# GNSS_MB.net
KiCad netlist of a schematic drawn in Altium Designer
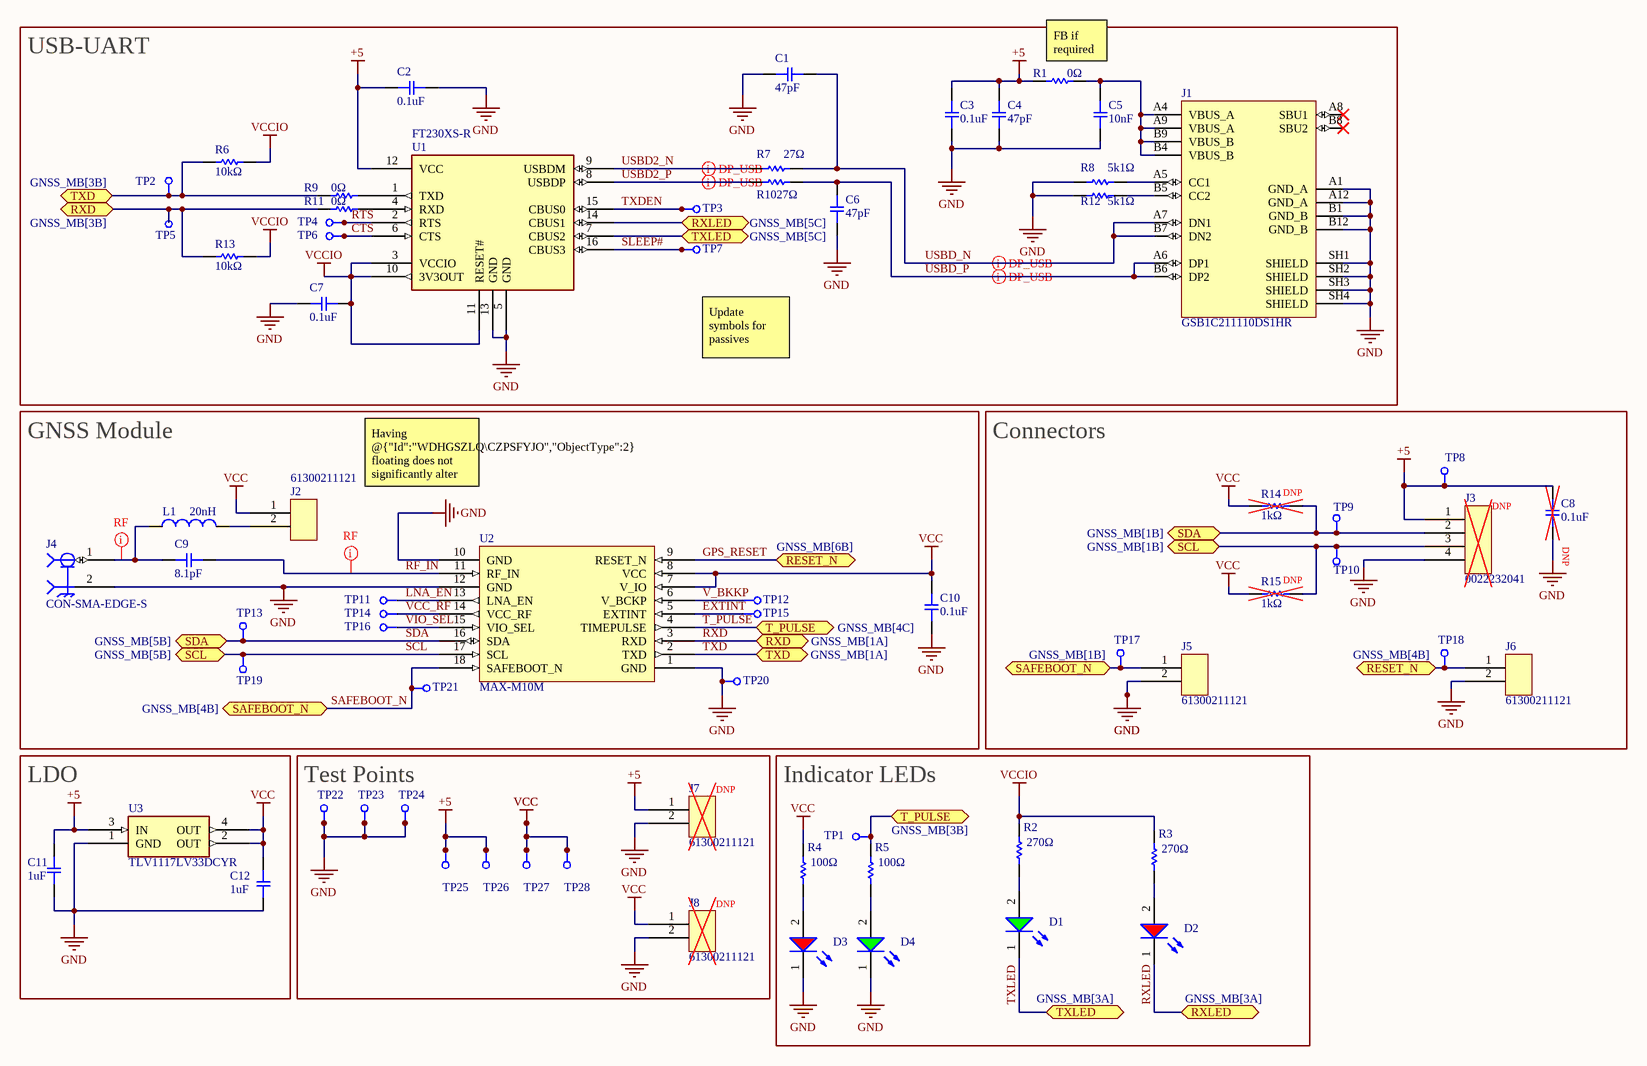
[diagram p0: GNSS_MB.SchDoc]

(export (version "E")
  (design (tool "Eeschema 10.0.6"))
  (components
    (comp (ref "C1")
      (value "GCM188L81H104KA57D")
      (footprint "CAP_MURATA_0603")
      (description "CAP CER 0.1UF 50V X8L 0603")
      (fields (field (name "CAPACITANCE") "47pF"))
      (libsource (lib "Symbols") (part "GCM188L81H104KA57D"))
    )
    (comp (ref "C2")
      (value "GCM188L81H104KA57D")
      (footprint "CAP_MURATA_0603")
      (description "CAP CER 0.1UF 50V X8L 0603")
      (fields (field (name "CAPACITANCE") "0.1uF"))
      (libsource (lib "Symbols") (part "GCM188L81H104KA57D"))
    )
    (comp (ref "C3")
      (value "GCM188L81H104KA57D")
      (footprint "CAP_MURATA_0603")
      (description "CAP CER 0.1UF 50V X8L 0603")
      (fields (field (name "CAPACITANCE") "0.1uF"))
      (libsource (lib "Symbols") (part "GCM188L81H104KA57D"))
    )
    (comp (ref "C4")
      (value "GCM188L81H104KA57D")
      (footprint "CAP_MURATA_0603")
      (description "CAP CER 0.1UF 50V X8L 0603")
      (fields (field (name "CAPACITANCE") "47pF"))
      (libsource (lib "Symbols") (part "GCM188L81H104KA57D"))
    )
    (comp (ref "C5")
      (value "GCM188L81H104KA57D")
      (footprint "CAP_MURATA_0603")
      (description "CAP CER 0.1UF 50V X8L 0603")
      (fields (field (name "CAPACITANCE") "10nF"))
      (libsource (lib "Symbols") (part "GCM188L81H104KA57D"))
    )
    (comp (ref "C6")
      (value "GCM188L81H104KA57D")
      (footprint "CAP_MURATA_0603")
      (description "CAP CER 0.1UF 50V X8L 0603")
      (fields (field (name "CAPACITANCE") "47pF"))
      (libsource (lib "Symbols") (part "GCM188L81H104KA57D"))
    )
    (comp (ref "C7")
      (value "GCM188L81H104KA57D")
      (footprint "CAP_MURATA_0603")
      (description "CAP CER 0.1UF 50V X8L 0603")
      (fields (field (name "CAPACITANCE") "0.1uF"))
      (libsource (lib "Symbols") (part "GCM188L81H104KA57D"))
    )
    (comp (ref "C8")
      (value "GCM188L81H104KA57D")
      (footprint "CAP_MURATA_0603")
      (description "CAP CER 0.1UF 50V X8L 0603")
      (fields (field (name "CAPACITANCE") "0.1uF"))
      (libsource (lib "Symbols") (part "GCM188L81H104KA57D"))
    )
    (comp (ref "C9")
      (value "GCM188L81H104KA57D")
      (footprint "CAP_MURATA_0603")
      (description "CAP CER 0.1UF 50V X8L 0603")
      (fields (field (name "CAPACITANCE") "8.1pF"))
      (libsource (lib "Symbols") (part "GCM188L81H104KA57D"))
    )
    (comp (ref "C10")
      (value "GCM188L81H104KA57D")
      (footprint "CAP_MURATA_0603")
      (description "CAP CER 0.1UF 50V X8L 0603")
      (fields (field (name "CAPACITANCE") "0.1uF"))
      (libsource (lib "Symbols") (part "GCM188L81H104KA57D"))
    )
    (comp (ref "C11")
      (value "GRM188R61A105KA61D")
      (footprint "CAP_MURATA_0603")
      (description "CAP CER 1UF 10V X5R 0603")
      (fields (field (name "CAPACITANCE") "1uF"))
      (libsource (lib "Symbols") (part "GRM188R61A105KA61D"))
    )
    (comp (ref "C12")
      (value "GRM188R61A105KA61D")
      (footprint "CAP_MURATA_0603")
      (description "CAP CER 1UF 10V X5R 0603")
      (fields (field (name "CAPACITANCE") "1uF"))
      (libsource (lib "Symbols") (part "GRM188R61A105KA61D"))
    )
    (comp (ref "D1")
      (value "Green, 3.2V, 140°")
      (footprint "WL-SMCW - duplicate")
      (description "WL-SMCW Mono-color Chip LED Waterclear, SMT, size 0603, Green, 3.2V, 140°")
      (fields
        (field (name "MANUFACTURER PART NUMBER") "150060GS75000")
        (field (name "MANUFACTURER") "Wurth Elektronik")
      )
      (libsource (lib "Symbols") (part "150060GS75000"))
    )
    (comp (ref "D2")
      (value "Red, 2V, 140°")
      (footprint "WL-SMCW - duplicate")
      (description "WL-SMCW Mono-color Chip LED Waterclear, SMT, size 0603, Red, 2V, 140°")
      (fields
        (field (name "MANUFACTURER PART NUMBER") "150060RS75000")
        (field (name "MANUFACTURER") "Wurth Elektronik")
      )
      (libsource (lib "Symbols") (part "150060RS75000"))
    )
    (comp (ref "D3")
      (value "Red, 2V, 140°")
      (footprint "WL-SMCW - duplicate")
      (description "WL-SMCW Mono-color Chip LED Waterclear, SMT, size 0603, Red, 2V, 140°")
      (fields
        (field (name "MANUFACTURER PART NUMBER") "150060RS75000")
        (field (name "MANUFACTURER") "Wurth Elektronik")
      )
      (libsource (lib "Symbols") (part "150060RS75000"))
    )
    (comp (ref "D4")
      (value "Green, 3.2V, 140°")
      (footprint "WL-SMCW - duplicate")
      (description "WL-SMCW Mono-color Chip LED Waterclear, SMT, size 0603, Green, 3.2V, 140°")
      (fields
        (field (name "MANUFACTURER PART NUMBER") "150060GS75000")
        (field (name "MANUFACTURER") "Wurth Elektronik")
      )
      (libsource (lib "Symbols") (part "150060GS75000"))
    )
    (comp (ref "J1")
      (value "GSB1C211110DS1HR")
      (footprint "AMPHENOL_GSB1C211110DS1HR")
      (description "USB2.0, Type C, Top mount, Center Height 1.78mm, Dual Row DIP")
      (fields (field (name "MF") "Amphenol Canada"))
      (libsource (lib "Symbols") (part "GSB1C211110DS1HR"))
    )
    (comp (ref "J2")
      (value "61300211121")
      (footprint "61300211121")
      (description "CONN HEADER VERT 2POS 2.54MM")
      (libsource (lib "Symbols") (part "61300211121"))
    )
    (comp (ref "J3")
      (value "0022232041")
      (footprint "CONN HEADER VERT 4POS 2.54MM")
      (description "CONN HEADER VERT 4POS 2.54MM")
      (libsource (lib "Symbols") (part "0022232041"))
    )
    (comp (ref "J4")
      (value "CON-SMA-EDGE-S")
      (footprint "RFSOLUTIONS_CON-SMA-EDGE-S")
      (description "CONN SMA JACK STR EDGE MNT")
      (libsource (lib "Symbols") (part "CON-SMA-EDGE-S"))
    )
    (comp (ref "J5")
      (value "61300211121")
      (footprint "61300211121")
      (description "CONN HEADER VERT 2POS 2.54MM")
      (libsource (lib "Symbols") (part "61300211121"))
    )
    (comp (ref "J6")
      (value "61300211121")
      (footprint "61300211121")
      (description "CONN HEADER VERT 2POS 2.54MM")
      (libsource (lib "Symbols") (part "61300211121"))
    )
    (comp (ref "J7")
      (value "61300211121")
      (footprint "61300211121")
      (description "CONN HEADER VERT 2POS 2.54MM")
      (libsource (lib "Symbols") (part "61300211121"))
    )
    (comp (ref "J8")
      (value "61300211121")
      (footprint "61300211121")
      (description "CONN HEADER VERT 2POS 2.54MM")
      (libsource (lib "Symbols") (part "61300211121"))
    )
    (comp (ref "L1")
      (value "20nH")
      (footprint "INDC1006X60N")
      (description "FIXED IND 3.6NH 900MA 40 MOHM")
      (fields (field (name "MP") "LQW15AN3N6C10D"))
      (libsource (lib "Symbols") (part "LQW15AN3N6C10D"))
    )
    (comp (ref "R1")
      (value "RC0603JR-070RL")
      (footprint "RC0603JR-070RL")
      (description "Chip Resistor, 0 Ohm, +/- 5%, 0.1 W, -55 to 155 degC, 0603 (1608 Metric), RoHS, Tape and Reel")
      (fields
        (field (name "TOLERANCE") "5%")
        (field (name "RESISTANCE") "0Ω")
        (field (name "MANUFACTURER") "Yageo")
      )
      (libsource (lib "Symbols") (part "RC0603JR-070RL"))
    )
    (comp (ref "R2")
      (value "RC0603JR-070RL")
      (footprint "RC0603JR-070RL")
      (description "Chip Resistor, 0 Ohm, +/- 5%, 0.1 W, -55 to 155 degC, 0603 (1608 Metric), RoHS, Tape and Reel")
      (fields
        (field (name "TOLERANCE") "5%")
        (field (name "RESISTANCE") "270Ω")
        (field (name "MANUFACTURER") "Yageo")
      )
      (libsource (lib "Symbols") (part "RC0603JR-070RL"))
    )
    (comp (ref "R3")
      (value "RC0603JR-070RL")
      (footprint "RC0603JR-070RL")
      (description "Chip Resistor, 0 Ohm, +/- 5%, 0.1 W, -55 to 155 degC, 0603 (1608 Metric), RoHS, Tape and Reel")
      (fields
        (field (name "TOLERANCE") "5%")
        (field (name "RESISTANCE") "270Ω")
        (field (name "MANUFACTURER") "Yageo")
      )
      (libsource (lib "Symbols") (part "RC0603JR-070RL"))
    )
    (comp (ref "R4")
      (value "RC0603JR-070RL")
      (footprint "RC0603JR-070RL")
      (description "Chip Resistor, 0 Ohm, +/- 5%, 0.1 W, -55 to 155 degC, 0603 (1608 Metric), RoHS, Tape and Reel")
      (fields
        (field (name "TOLERANCE") "5%")
        (field (name "RESISTANCE") "100Ω")
        (field (name "MANUFACTURER") "Yageo")
      )
      (libsource (lib "Symbols") (part "RC0603JR-070RL"))
    )
    (comp (ref "R5")
      (value "RC0603JR-070RL")
      (footprint "RC0603JR-070RL")
      (description "Chip Resistor, 0 Ohm, +/- 5%, 0.1 W, -55 to 155 degC, 0603 (1608 Metric), RoHS, Tape and Reel")
      (fields
        (field (name "TOLERANCE") "5%")
        (field (name "RESISTANCE") "100Ω")
        (field (name "MANUFACTURER") "Yageo")
      )
      (libsource (lib "Symbols") (part "RC0603JR-070RL"))
    )
    (comp (ref "R6")
      (value "RC0603JR-070RL")
      (footprint "RC0603JR-070RL")
      (description "Chip Resistor, 0 Ohm, +/- 5%, 0.1 W, -55 to 155 degC, 0603 (1608 Metric), RoHS, Tape and Reel")
      (fields
        (field (name "TOLERANCE") "5%")
        (field (name "RESISTANCE") "10kΩ")
        (field (name "MANUFACTURER") "Yageo")
      )
      (libsource (lib "Symbols") (part "RC0603JR-070RL"))
    )
    (comp (ref "R7")
      (value "RC0603JR-070RL")
      (footprint "RC0603JR-070RL")
      (description "Chip Resistor, 0 Ohm, +/- 5%, 0.1 W, -55 to 155 degC, 0603 (1608 Metric), RoHS, Tape and Reel")
      (fields
        (field (name "TOLERANCE") "5%")
        (field (name "RESISTANCE") "27Ω")
        (field (name "MANUFACTURER") "Yageo")
      )
      (libsource (lib "Symbols") (part "RC0603JR-070RL"))
    )
    (comp (ref "R8")
      (value "RC0603JR-070RL")
      (footprint "RC0603JR-070RL")
      (description "Chip Resistor, 0 Ohm, +/- 5%, 0.1 W, -55 to 155 degC, 0603 (1608 Metric), RoHS, Tape and Reel")
      (fields
        (field (name "TOLERANCE") "5%")
        (field (name "RESISTANCE") "5k1Ω")
        (field (name "MANUFACTURER") "Yageo")
      )
      (libsource (lib "Symbols") (part "RC0603JR-070RL"))
    )
    (comp (ref "R9")
      (value "RC0603JR-070RL")
      (footprint "RC0603JR-070RL")
      (description "Chip Resistor, 0 Ohm, +/- 5%, 0.1 W, -55 to 155 degC, 0603 (1608 Metric), RoHS, Tape and Reel")
      (fields
        (field (name "TOLERANCE") "5%")
        (field (name "RESISTANCE") "0Ω")
        (field (name "MANUFACTURER") "Yageo")
      )
      (libsource (lib "Symbols") (part "RC0603JR-070RL"))
    )
    (comp (ref "R10")
      (value "RC0603JR-070RL")
      (footprint "RC0603JR-070RL")
      (description "Chip Resistor, 0 Ohm, +/- 5%, 0.1 W, -55 to 155 degC, 0603 (1608 Metric), RoHS, Tape and Reel")
      (fields
        (field (name "TOLERANCE") "5%")
        (field (name "RESISTANCE") "27Ω")
        (field (name "MANUFACTURER") "Yageo")
      )
      (libsource (lib "Symbols") (part "RC0603JR-070RL"))
    )
    (comp (ref "R11")
      (value "RC0603JR-070RL")
      (footprint "RC0603JR-070RL")
      (description "Chip Resistor, 0 Ohm, +/- 5%, 0.1 W, -55 to 155 degC, 0603 (1608 Metric), RoHS, Tape and Reel")
      (fields
        (field (name "TOLERANCE") "5%")
        (field (name "RESISTANCE") "0Ω")
        (field (name "MANUFACTURER") "Yageo")
      )
      (libsource (lib "Symbols") (part "RC0603JR-070RL"))
    )
    (comp (ref "R12")
      (value "RC0603JR-070RL")
      (footprint "RC0603JR-070RL")
      (description "Chip Resistor, 0 Ohm, +/- 5%, 0.1 W, -55 to 155 degC, 0603 (1608 Metric), RoHS, Tape and Reel")
      (fields
        (field (name "TOLERANCE") "5%")
        (field (name "RESISTANCE") "5k1Ω")
        (field (name "MANUFACTURER") "Yageo")
      )
      (libsource (lib "Symbols") (part "RC0603JR-070RL"))
    )
    (comp (ref "R13")
      (value "RC0603JR-070RL")
      (footprint "RC0603JR-070RL")
      (description "Chip Resistor, 0 Ohm, +/- 5%, 0.1 W, -55 to 155 degC, 0603 (1608 Metric), RoHS, Tape and Reel")
      (fields
        (field (name "TOLERANCE") "5%")
        (field (name "RESISTANCE") "10kΩ")
        (field (name "MANUFACTURER") "Yageo")
      )
      (libsource (lib "Symbols") (part "RC0603JR-070RL"))
    )
    (comp (ref "R14")
      (value "RC0603JR-070RL")
      (footprint "RC0603JR-070RL")
      (description "Chip Resistor, 0 Ohm, +/- 5%, 0.1 W, -55 to 155 degC, 0603 (1608 Metric), RoHS, Tape and Reel")
      (fields
        (field (name "TOLERANCE") "5%")
        (field (name "RESISTANCE") "1kΩ")
        (field (name "MANUFACTURER") "Yageo")
      )
      (libsource (lib "Symbols") (part "RC0603JR-070RL"))
    )
    (comp (ref "R15")
      (value "RC0603JR-070RL")
      (footprint "RC0603JR-070RL")
      (description "Chip Resistor, 0 Ohm, +/- 5%, 0.1 W, -55 to 155 degC, 0603 (1608 Metric), RoHS, Tape and Reel")
      (fields
        (field (name "TOLERANCE") "5%")
        (field (name "RESISTANCE") "1kΩ")
        (field (name "MANUFACTURER") "Yageo")
      )
      (libsource (lib "Symbols") (part "RC0603JR-070RL"))
    )
    (comp (ref "TP1")
      (value "TEST_POINT")
      (footprint "TEST_POINT")
      (description "TEST POINT 2MM")
      (libsource (lib "Symbols") (part "TEST_POINT"))
    )
    (comp (ref "TP2")
      (value "TEST_POINT")
      (footprint "TEST_POINT")
      (description "TEST POINT 2MM")
      (libsource (lib "Symbols") (part "TEST_POINT"))
    )
    (comp (ref "TP3")
      (value "TEST_POINT")
      (footprint "TEST_POINT")
      (description "TEST POINT 2MM")
      (libsource (lib "Symbols") (part "TEST_POINT"))
    )
    (comp (ref "TP4")
      (value "TEST_POINT")
      (footprint "TEST_POINT")
      (description "TEST POINT 2MM")
      (libsource (lib "Symbols") (part "TEST_POINT"))
    )
    (comp (ref "TP5")
      (value "TEST_POINT")
      (footprint "TEST_POINT")
      (description "TEST POINT 2MM")
      (libsource (lib "Symbols") (part "TEST_POINT"))
    )
    (comp (ref "TP6")
      (value "TEST_POINT")
      (footprint "TEST_POINT")
      (description "TEST POINT 2MM")
      (libsource (lib "Symbols") (part "TEST_POINT"))
    )
    (comp (ref "TP7")
      (value "TEST_POINT")
      (footprint "TEST_POINT")
      (description "TEST POINT 2MM")
      (libsource (lib "Symbols") (part "TEST_POINT"))
    )
    (comp (ref "TP8")
      (value "TEST_POINT")
      (footprint "TEST_POINT")
      (description "TEST POINT 2MM")
      (libsource (lib "Symbols") (part "TEST_POINT"))
    )
    (comp (ref "TP9")
      (value "TEST_POINT")
      (footprint "TEST_POINT")
      (description "TEST POINT 2MM")
      (libsource (lib "Symbols") (part "TEST_POINT"))
    )
    (comp (ref "TP10")
      (value "TEST_POINT")
      (footprint "TEST_POINT")
      (description "TEST POINT 2MM")
      (libsource (lib "Symbols") (part "TEST_POINT"))
    )
    (comp (ref "TP11")
      (value "TEST_POINT")
      (footprint "TEST_POINT")
      (description "TEST POINT 2MM")
      (libsource (lib "Symbols") (part "TEST_POINT"))
    )
    (comp (ref "TP12")
      (value "TEST_POINT")
      (footprint "TEST_POINT")
      (description "TEST POINT 2MM")
      (libsource (lib "Symbols") (part "TEST_POINT"))
    )
    (comp (ref "TP13")
      (value "TEST_POINT")
      (footprint "TEST_POINT")
      (description "TEST POINT 2MM")
      (libsource (lib "Symbols") (part "TEST_POINT"))
    )
    (comp (ref "TP14")
      (value "TEST_POINT")
      (footprint "TEST_POINT")
      (description "TEST POINT 2MM")
      (libsource (lib "Symbols") (part "TEST_POINT"))
    )
    (comp (ref "TP15")
      (value "TEST_POINT")
      (footprint "TEST_POINT")
      (description "TEST POINT 2MM")
      (libsource (lib "Symbols") (part "TEST_POINT"))
    )
    (comp (ref "TP16")
      (value "TEST_POINT")
      (footprint "TEST_POINT")
      (description "TEST POINT 2MM")
      (libsource (lib "Symbols") (part "TEST_POINT"))
    )
    (comp (ref "TP17")
      (value "TEST_POINT")
      (footprint "TEST_POINT")
      (description "TEST POINT 2MM")
      (libsource (lib "Symbols") (part "TEST_POINT"))
    )
    (comp (ref "TP18")
      (value "TEST_POINT")
      (footprint "TEST_POINT")
      (description "TEST POINT 2MM")
      (libsource (lib "Symbols") (part "TEST_POINT"))
    )
    (comp (ref "TP19")
      (value "TEST_POINT")
      (footprint "TEST_POINT")
      (description "TEST POINT 2MM")
      (libsource (lib "Symbols") (part "TEST_POINT"))
    )
    (comp (ref "TP20")
      (value "TEST_POINT")
      (footprint "TEST_POINT")
      (description "TEST POINT 2MM")
      (libsource (lib "Symbols") (part "TEST_POINT"))
    )
    (comp (ref "TP21")
      (value "TEST_POINT")
      (footprint "TEST_POINT")
      (description "TEST POINT 2MM")
      (libsource (lib "Symbols") (part "TEST_POINT"))
    )
    (comp (ref "TP22")
      (value "TEST_POINT")
      (footprint "TEST_POINT")
      (description "TEST POINT 2MM")
      (libsource (lib "Symbols") (part "TEST_POINT"))
    )
    (comp (ref "TP23")
      (value "TEST_POINT")
      (footprint "TEST_POINT")
      (description "TEST POINT 2MM")
      (libsource (lib "Symbols") (part "TEST_POINT"))
    )
    (comp (ref "TP24")
      (value "TEST_POINT")
      (footprint "TEST_POINT")
      (description "TEST POINT 2MM")
      (libsource (lib "Symbols") (part "TEST_POINT"))
    )
    (comp (ref "TP25")
      (value "TEST_POINT")
      (footprint "TEST_POINT")
      (description "TEST POINT 2MM")
      (libsource (lib "Symbols") (part "TEST_POINT"))
    )
    (comp (ref "TP26")
      (value "TEST_POINT")
      (footprint "TEST_POINT")
      (description "TEST POINT 2MM")
      (libsource (lib "Symbols") (part "TEST_POINT"))
    )
    (comp (ref "TP27")
      (value "TEST_POINT")
      (footprint "TEST_POINT")
      (description "TEST POINT 2MM")
      (libsource (lib "Symbols") (part "TEST_POINT"))
    )
    (comp (ref "TP28")
      (value "TEST_POINT")
      (footprint "TEST_POINT")
      (description "TEST POINT 2MM")
      (libsource (lib "Symbols") (part "TEST_POINT"))
    )
    (comp (ref "U1")
      (value "FT230XS-R")
      (footprint "FT230XS-R")
      (description "USB FULL SPEED TO SERIAL UART IC")
      (libsource (lib "Symbols") (part "FT230XS-R"))
    )
    (comp (ref "U2")
      (value "MAX-M10M")
      (footprint "MAX-M10M")
      (description "GNSS LCC RX MOD, ROM, CRYSTAL")
      (libsource (lib "Symbols") (part "MAX-M10M"))
    )
    (comp (ref "U3")
      (value "TLV1117LV33DCYR")
      (footprint "TLV1117LV33DCYR")
      (description "IC REG LINEAR 3.3V 1A SOT223-4")
      (libsource (lib "Symbols") (part "TLV1117LV33DCYR"))
    )
  )
  (nets
    (net (code "1") (name "+5") (class "Default")
      (node (ref "C11") (pin "2") (pinfunction "2_2") (pintype "passive"))
      (node (ref "C2") (pin "2") (pinfunction "2_2") (pintype "passive"))
      (node (ref "C3") (pin "1") (pinfunction "1_1") (pintype "passive"))
      (node (ref "C4") (pin "1") (pinfunction "1_1") (pintype "passive"))
      (node (ref "C8") (pin "1") (pinfunction "1_1") (pintype "passive"))
      (node (ref "J3") (pin "1") (pintype "passive"))
      (node (ref "J7") (pin "1") (pintype "passive"))
      (node (ref "R1") (pin "1") (pinfunction "1_1") (pintype "passive"))
      (node (ref "TP25") (pin "1") (pinfunction "1_1") (pintype "passive"))
      (node (ref "TP26") (pin "1") (pinfunction "1_1") (pintype "passive"))
      (node (ref "TP8") (pin "1") (pinfunction "1_1") (pintype "passive"))
      (node (ref "U1") (pin "12") (pinfunction "VCC_12") (pintype "power_in"))
      (node (ref "U3") (pin "3") (pinfunction "IN_3") (pintype "input"))
    )
    (net (code "2") (name "/CTS") (class "Default")
      (node (ref "TP6") (pin "1") (pinfunction "1_1") (pintype "passive"))
      (node (ref "U1") (pin "6") (pinfunction "CTS_6") (pintype "input"))
    )
    (net (code "3") (name "/EXTINT") (class "Default")
      (node (ref "TP15") (pin "1") (pinfunction "1_1") (pintype "passive"))
      (node (ref "U2") (pin "5") (pinfunction "EXTINT_5") (pintype "input"))
    )
    (net (code "4") (name "/GPS_RESET") (class "Default")
      (node (ref "J6") (pin "1") (pintype "passive"))
      (node (ref "TP18") (pin "1") (pinfunction "1_1") (pintype "passive"))
      (node (ref "U2") (pin "9") (pinfunction "RESET_N_9") (pintype "input"))
    )
    (net (code "5") (name "/LNA_EN") (class "Default")
      (node (ref "TP11") (pin "1") (pinfunction "1_1") (pintype "passive"))
      (node (ref "U2") (pin "13") (pinfunction "LNA_EN_13") (pintype "output"))
    )
    (net (code "6") (name "/RF_IN") (class "Default")
      (node (ref "C9") (pin "2") (pinfunction "2_2") (pintype "passive"))
      (node (ref "U2") (pin "11") (pinfunction "RF_IN_11") (pintype "input"))
    )
    (net (code "7") (name "/RTS") (class "Default")
      (node (ref "TP4") (pin "1") (pinfunction "1_1") (pintype "passive"))
      (node (ref "U1") (pin "2") (pinfunction "RTS_2") (pintype "output"))
    )
    (net (code "8") (name "/RXD") (class "Default")
      (node (ref "R11") (pin "1") (pinfunction "1_1") (pintype "passive"))
      (node (ref "R13") (pin "1") (pinfunction "1_1") (pintype "passive"))
      (node (ref "TP5") (pin "1") (pinfunction "1_1") (pintype "passive"))
      (node (ref "U2") (pin "3") (pinfunction "RXD_3") (pintype "input"))
    )
    (net (code "9") (name "/RXLED") (class "Default")
      (node (ref "D2") (pin "1") (pinfunction "K_1") (pintype "passive"))
      (node (ref "U1") (pin "14") (pinfunction "CBUS1_14") (pintype "bidirectional"))
    )
    (net (code "10") (name "/SAFEBOOT_N") (class "Default")
      (node (ref "J5") (pin "1") (pintype "passive"))
      (node (ref "TP17") (pin "1") (pinfunction "1_1") (pintype "passive"))
      (node (ref "TP21") (pin "1") (pinfunction "1_1") (pintype "passive"))
      (node (ref "U2") (pin "18") (pinfunction "SAFEBOOT_N_18") (pintype "input"))
    )
    (net (code "11") (name "/SCL") (class "Default")
      (node (ref "J3") (pin "3") (pintype "passive"))
      (node (ref "R15") (pin "1") (pinfunction "1_1") (pintype "passive"))
      (node (ref "TP10") (pin "1") (pinfunction "1_1") (pintype "passive"))
      (node (ref "TP19") (pin "1") (pinfunction "1_1") (pintype "passive"))
      (node (ref "U2") (pin "17") (pinfunction "SCL_17") (pintype "input"))
    )
    (net (code "12") (name "/SDA") (class "Default")
      (node (ref "J3") (pin "2") (pintype "passive"))
      (node (ref "R14") (pin "1") (pinfunction "1_1") (pintype "passive"))
      (node (ref "TP13") (pin "1") (pinfunction "1_1") (pintype "passive"))
      (node (ref "TP9") (pin "1") (pinfunction "1_1") (pintype "passive"))
      (node (ref "U2") (pin "16") (pinfunction "SDA_16") (pintype "bidirectional"))
    )
    (net (code "13") (name "/SLEEP#") (class "Default")
      (node (ref "TP7") (pin "1") (pinfunction "1_1") (pintype "passive"))
      (node (ref "U1") (pin "16") (pinfunction "CBUS3_16") (pintype "bidirectional"))
    )
    (net (code "14") (name "/TXD") (class "Default")
      (node (ref "R6") (pin "1") (pinfunction "1_1") (pintype "passive"))
      (node (ref "R9") (pin "1") (pinfunction "1_1") (pintype "passive"))
      (node (ref "TP2") (pin "1") (pinfunction "1_1") (pintype "passive"))
      (node (ref "U2") (pin "2") (pinfunction "TXD_2") (pintype "output"))
    )
    (net (code "15") (name "/TXDEN") (class "Default")
      (node (ref "TP3") (pin "1") (pinfunction "1_1") (pintype "passive"))
      (node (ref "U1") (pin "15") (pinfunction "CBUS0_15") (pintype "bidirectional"))
    )
    (net (code "16") (name "/TXLED") (class "Default")
      (node (ref "D1") (pin "1") (pinfunction "K_1") (pintype "passive"))
      (node (ref "U1") (pin "7") (pinfunction "CBUS2_7") (pintype "bidirectional"))
    )
    (net (code "17") (name "/T_PULSE") (class "Default")
      (node (ref "R5") (pin "2") (pinfunction "2_2") (pintype "passive"))
      (node (ref "TP1") (pin "1") (pinfunction "1_1") (pintype "passive"))
      (node (ref "U2") (pin "4") (pinfunction "TIMEPULSE_4") (pintype "output"))
    )
    (net (code "18") (name "/USBD2_N") (class "Default")
      (node (ref "R7") (pin "1") (pinfunction "1_1") (pintype "passive"))
      (node (ref "U1") (pin "9") (pinfunction "USBDM_9") (pintype "bidirectional"))
    )
    (net (code "19") (name "/USBD2_P") (class "Default")
      (node (ref "R10") (pin "1") (pinfunction "1_1") (pintype "passive"))
      (node (ref "U1") (pin "8") (pinfunction "USBDP_8") (pintype "bidirectional"))
    )
    (net (code "20") (name "/USBD_N") (class "Default")
      (node (ref "C1") (pin "2") (pinfunction "2_2") (pintype "passive"))
      (node (ref "J1") (pin "A7") (pinfunction "DN1_A7") (pintype "bidirectional"))
      (node (ref "J1") (pin "B7") (pinfunction "DN2_B7") (pintype "bidirectional"))
      (node (ref "R7") (pin "2") (pinfunction "2_2") (pintype "passive"))
    )
    (net (code "21") (name "/USBD_P") (class "Default")
      (node (ref "C6") (pin "1") (pinfunction "1_1") (pintype "passive"))
      (node (ref "J1") (pin "A6") (pinfunction "DP1_A6") (pintype "bidirectional"))
      (node (ref "J1") (pin "B6") (pinfunction "DP2_B6") (pintype "bidirectional"))
      (node (ref "R10") (pin "2") (pinfunction "2_2") (pintype "passive"))
    )
    (net (code "22") (name "/VCC_RF") (class "Default")
      (node (ref "TP14") (pin "1") (pinfunction "1_1") (pintype "passive"))
      (node (ref "U2") (pin "14") (pinfunction "VCC_RF_14") (pintype "output"))
    )
    (net (code "23") (name "/VIO_SEL") (class "Default")
      (node (ref "TP16") (pin "1") (pinfunction "1_1") (pintype "passive"))
      (node (ref "U2") (pin "15") (pinfunction "VIO_SEL_15") (pintype "input"))
    )
    (net (code "24") (name "/V_BKKP") (class "Default")
      (node (ref "TP12") (pin "1") (pinfunction "1_1") (pintype "passive"))
      (node (ref "U2") (pin "6") (pinfunction "V_BCKP_6") (pintype "input"))
    )
    (net (code "25") (name "GND") (class "Default")
      (node (ref "C1") (pin "1") (pinfunction "1_1") (pintype "passive"))
      (node (ref "C10") (pin "1") (pinfunction "1_1") (pintype "passive"))
      (node (ref "C11") (pin "1") (pinfunction "1_1") (pintype "passive"))
      (node (ref "C12") (pin "1") (pinfunction "1_1") (pintype "passive"))
      (node (ref "C2") (pin "1") (pinfunction "1_1") (pintype "passive"))
      (node (ref "C3") (pin "2") (pinfunction "2_2") (pintype "passive"))
      (node (ref "C4") (pin "2") (pinfunction "2_2") (pintype "passive"))
      (node (ref "C5") (pin "2") (pinfunction "2_2") (pintype "passive"))
      (node (ref "C6") (pin "2") (pinfunction "2_2") (pintype "passive"))
      (node (ref "C7") (pin "2") (pinfunction "2_2") (pintype "passive"))
      (node (ref "C8") (pin "2") (pinfunction "2_2") (pintype "passive"))
      (node (ref "D3") (pin "1") (pinfunction "K_1") (pintype "passive"))
      (node (ref "D4") (pin "1") (pinfunction "K_1") (pintype "passive"))
      (node (ref "J1") (pin "A1") (pinfunction "GND_A_A1") (pintype "power_in"))
      (node (ref "J1") (pin "A12") (pinfunction "GND_A_A12") (pintype "power_in"))
      (node (ref "J1") (pin "B1") (pinfunction "GND_B_B1") (pintype "power_in"))
      (node (ref "J1") (pin "B12") (pinfunction "GND_B_B12") (pintype "power_in"))
      (node (ref "J1") (pin "SH1") (pinfunction "SHIELD_SH1") (pintype "passive"))
      (node (ref "J1") (pin "SH2") (pinfunction "SHIELD_SH2") (pintype "passive"))
      (node (ref "J1") (pin "SH3") (pinfunction "SHIELD_SH3") (pintype "passive"))
      (node (ref "J1") (pin "SH4") (pinfunction "SHIELD_SH4") (pintype "passive"))
      (node (ref "J3") (pin "4") (pintype "passive"))
      (node (ref "J4") (pin "2") (pinfunction "GND_2") (pintype "power_in"))
      (node (ref "J5") (pin "2") (pintype "passive"))
      (node (ref "J6") (pin "2") (pintype "passive"))
      (node (ref "J7") (pin "2") (pintype "passive"))
      (node (ref "J8") (pin "2") (pintype "passive"))
      (node (ref "R12") (pin "1") (pinfunction "1_1") (pintype "passive"))
      (node (ref "R8") (pin "1") (pinfunction "1_1") (pintype "passive"))
      (node (ref "TP20") (pin "1") (pinfunction "1_1") (pintype "passive"))
      (node (ref "TP22") (pin "1") (pinfunction "1_1") (pintype "passive"))
      (node (ref "TP23") (pin "1") (pinfunction "1_1") (pintype "passive"))
      (node (ref "TP24") (pin "1") (pinfunction "1_1") (pintype "passive"))
      (node (ref "U1") (pin "13") (pinfunction "GND_13") (pintype "power_in"))
      (node (ref "U1") (pin "5") (pinfunction "GND_5") (pintype "power_in"))
      (node (ref "U2") (pin "1") (pinfunction "GND_1") (pintype "power_in"))
      (node (ref "U2") (pin "10") (pinfunction "GND_10") (pintype "power_in"))
      (node (ref "U2") (pin "12") (pinfunction "GND_12") (pintype "power_in"))
      (node (ref "U3") (pin "1") (pinfunction "GND_1") (pintype "power_in"))
    )
    (net (code "26") (name "Net-(C5-Pad1)") (class "Default")
      (node (ref "C5") (pin "1") (pinfunction "1_1") (pintype "passive"))
      (node (ref "J1") (pin "A4") (pinfunction "VBUS_A_A4") (pintype "power_in"))
      (node (ref "J1") (pin "A9") (pinfunction "VBUS_A_A9") (pintype "power_in"))
      (node (ref "J1") (pin "B4") (pinfunction "VBUS_B_B4") (pintype "power_in"))
      (node (ref "J1") (pin "B9") (pinfunction "VBUS_B_B9") (pintype "power_in"))
      (node (ref "R1") (pin "2") (pinfunction "2_2") (pintype "passive"))
    )
    (net (code "27") (name "Net-(D1-A)") (class "Default")
      (node (ref "D1") (pin "2") (pinfunction "A_2") (pintype "passive"))
      (node (ref "R2") (pin "1") (pinfunction "1_1") (pintype "passive"))
    )
    (net (code "28") (name "Net-(D2-A)") (class "Default")
      (node (ref "D2") (pin "2") (pinfunction "A_2") (pintype "passive"))
      (node (ref "R3") (pin "1") (pinfunction "1_1") (pintype "passive"))
    )
    (net (code "29") (name "Net-(D3-A)") (class "Default")
      (node (ref "D3") (pin "2") (pinfunction "A_2") (pintype "passive"))
      (node (ref "R4") (pin "1") (pinfunction "1_1") (pintype "passive"))
    )
    (net (code "30") (name "Net-(D4-A)") (class "Default")
      (node (ref "D4") (pin "2") (pinfunction "A_2") (pintype "passive"))
      (node (ref "R5") (pin "1") (pinfunction "1_1") (pintype "passive"))
    )
    (net (code "31") (name "Net-(J1-CC1)") (class "Default")
      (node (ref "J1") (pin "A5") (pinfunction "CC1_A5") (pintype "bidirectional"))
      (node (ref "R8") (pin "2") (pinfunction "2_2") (pintype "passive"))
    )
    (net (code "32") (name "Net-(J1-CC2)") (class "Default")
      (node (ref "J1") (pin "B5") (pinfunction "CC2_B5") (pintype "bidirectional"))
      (node (ref "R12") (pin "2") (pinfunction "2_2") (pintype "passive"))
    )
    (net (code "33") (name "Net-(J2-Pad2)") (class "Default")
      (node (ref "J2") (pin "2") (pintype "passive"))
      (node (ref "L1") (pin "2") (pinfunction "2_2") (pintype "passive"))
    )
    (net (code "34") (name "Net-(J4-RF)") (class "Default")
      (node (ref "C9") (pin "1") (pinfunction "1_1") (pintype "passive"))
      (node (ref "J4") (pin "1") (pinfunction "RF_1") (pintype "bidirectional"))
      (node (ref "L1") (pin "1") (pinfunction "1_1") (pintype "passive"))
    )
    (net (code "35") (name "Net-(U1-RXD)") (class "Default")
      (node (ref "R11") (pin "2") (pinfunction "2_2") (pintype "passive"))
      (node (ref "U1") (pin "4") (pinfunction "RXD_4") (pintype "input"))
    )
    (net (code "36") (name "Net-(U1-TXD)") (class "Default")
      (node (ref "R9") (pin "2") (pinfunction "2_2") (pintype "passive"))
      (node (ref "U1") (pin "1") (pinfunction "TXD_1") (pintype "output"))
    )
    (net (code "37") (name "VCC") (class "Default")
      (node (ref "C10") (pin "2") (pinfunction "2_2") (pintype "passive"))
      (node (ref "C12") (pin "2") (pinfunction "2_2") (pintype "passive"))
      (node (ref "J2") (pin "1") (pintype "passive"))
      (node (ref "J8") (pin "1") (pintype "passive"))
      (node (ref "R14") (pin "2") (pinfunction "2_2") (pintype "passive"))
      (node (ref "R15") (pin "2") (pinfunction "2_2") (pintype "passive"))
      (node (ref "R4") (pin "2") (pinfunction "2_2") (pintype "passive"))
      (node (ref "TP27") (pin "1") (pinfunction "1_1") (pintype "passive"))
      (node (ref "TP28") (pin "1") (pinfunction "1_1") (pintype "passive"))
      (node (ref "U2") (pin "7") (pinfunction "V_IO_7") (pintype "input"))
      (node (ref "U2") (pin "8") (pinfunction "VCC_8") (pintype "input"))
      (node (ref "U3") (pin "2") (pinfunction "OUT_2") (pintype "output"))
      (node (ref "U3") (pin "4") (pinfunction "OUT_4") (pintype "output"))
    )
    (net (code "38") (name "VCCIO") (class "Default")
      (node (ref "C7") (pin "1") (pinfunction "1_1") (pintype "passive"))
      (node (ref "R13") (pin "2") (pinfunction "2_2") (pintype "passive"))
      (node (ref "R2") (pin "2") (pinfunction "2_2") (pintype "passive"))
      (node (ref "R3") (pin "2") (pinfunction "2_2") (pintype "passive"))
      (node (ref "R6") (pin "2") (pinfunction "2_2") (pintype "passive"))
      (node (ref "U1") (pin "10") (pinfunction "3V3OUT_10") (pintype "output"))
      (node (ref "U1") (pin "11") (pinfunction "RESET#_11") (pintype "power_in"))
      (node (ref "U1") (pin "3") (pinfunction "VCCIO_3") (pintype "power_in"))
    )
    (net (code "39") (name "unconnected-(J1-SBU1-PadA8)") (class "Default")
      (node (ref "J1") (pin "A8") (pinfunction "SBU1_A8") (pintype "bidirectional+no_connect"))
    )
    (net (code "40") (name "unconnected-(J1-SBU2-PadB8)") (class "Default")
      (node (ref "J1") (pin "B8") (pinfunction "SBU2_B8") (pintype "bidirectional+no_connect"))
    )
  )
)
